# biolab_rev3.net
KiCad netlist of a schematic drawn in Altium Designer
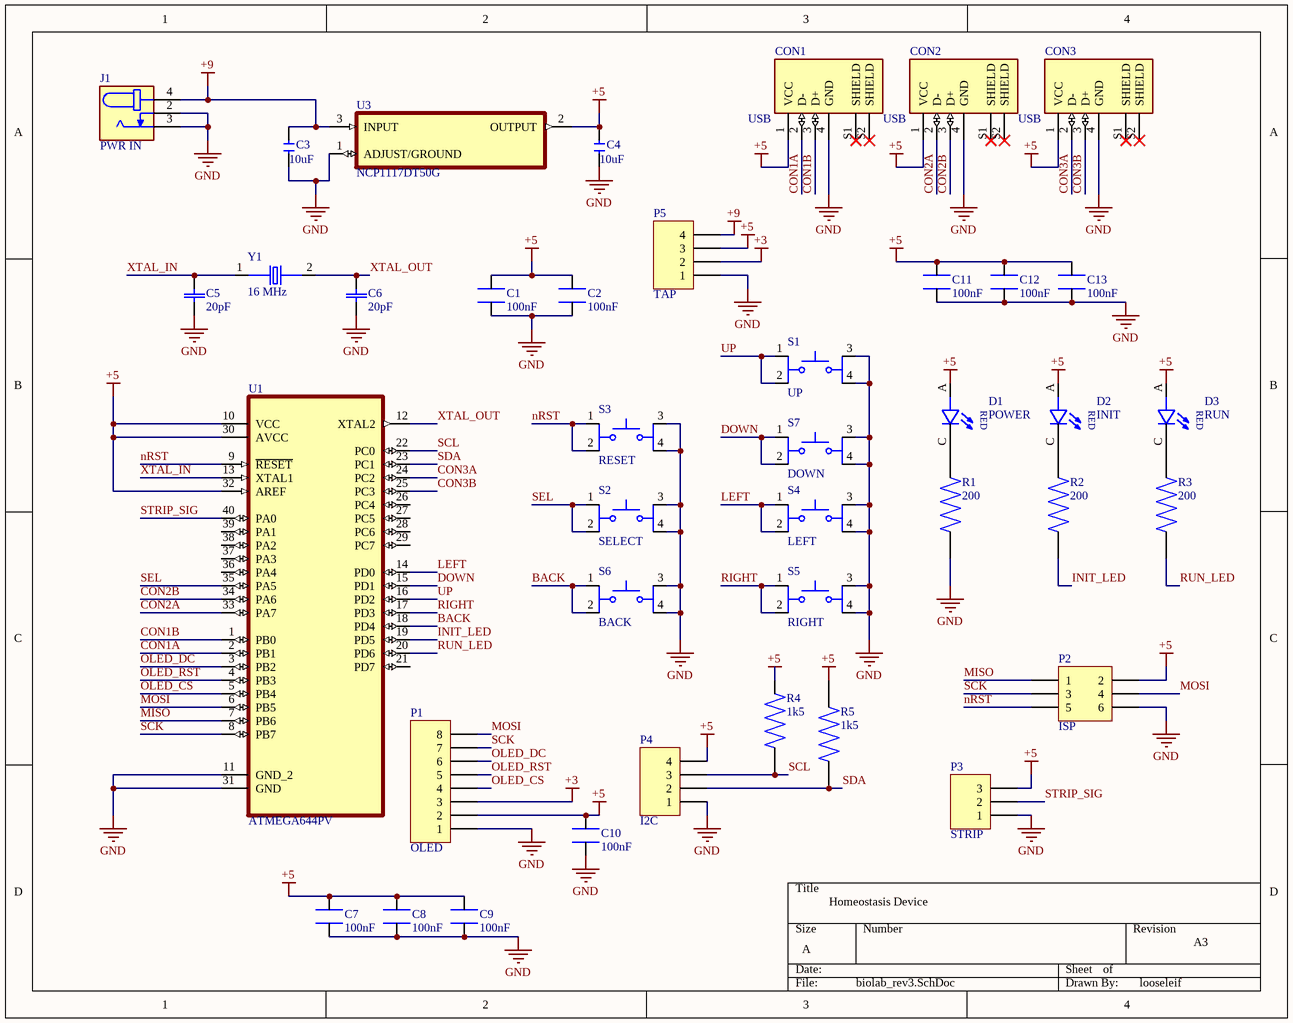
[diagram p0: biolab_rev3.SchDoc]

(export (version "E")
  (design (tool "Eeschema 10.0.6"))
  (components
    (comp (ref "C1")
      (value "100nF")
      (footprint "WCAP-CSST_885382206004")
      (fields
        (field (name "MP") "885382206004")
        (field (name "MF") "{'manufacturer': u'Wurth Electronics Inc'}")
      )
      (libsource (lib "biolab_interface") (part "885382206004"))
    )
    (comp (ref "C2")
      (value "100nF")
      (footprint "WCAP-CSST_885382206004")
      (fields
        (field (name "MP") "885382206004")
        (field (name "MF") "{'manufacturer': u'Wurth Electronics Inc'}")
      )
      (libsource (lib "biolab_interface") (part "885382206004"))
    )
    (comp (ref "C3")
      (value "10uF")
      (footprint "C0603")
      (description "302010103")
      (fields
        (field (name "MP") "CERAMIC-10UF-10V-10%-X5R(0603)")
        (field (name "MF") "{'manufacturer': u'Yageo'}")
      )
      (libsource (lib "SnapEDA_Library") (part "CERAMIC-10UF-10V-10%-X5R(0603)"))
    )
    (comp (ref "C4")
      (value "10uF")
      (footprint "C0603")
      (description "302010103")
      (fields
        (field (name "MP") "CERAMIC-10UF-10V-10%-X5R(0603)")
        (field (name "MF") "{'manufacturer': u'Yageo'}")
      )
      (libsource (lib "SnapEDA_Library") (part "CERAMIC-10UF-10V-10%-X5R(0603)"))
    )
    (comp (ref "C5")
      (value "20pF")
      (footprint "CAPC1608X85N")
      (description "CAPACITOR, 0603")
      (fields (field (name "MP") "C0603C200J5GACTU") (field (name "MF") "{'manufacturer': u'KEMET'}"))
      (libsource (lib "SnapEDA_Library") (part "C0603C200J5GACTU"))
    )
    (comp (ref "C6")
      (value "20pF")
      (footprint "CAPC1608X85N")
      (description "CAPACITOR, 0603")
      (fields (field (name "MP") "C0603C200J5GACTU") (field (name "MF") "{'manufacturer': u'KEMET'}"))
      (libsource (lib "SnapEDA_Library") (part "C0603C200J5GACTU"))
    )
    (comp (ref "C7")
      (value "100nF")
      (footprint "WCAP-CSST_885382206004")
      (fields
        (field (name "MP") "885382206004")
        (field (name "MF") "{'manufacturer': u'Wurth Electronics Inc'}")
      )
      (libsource (lib "biolab_interface") (part "885382206004"))
    )
    (comp (ref "C8")
      (value "100nF")
      (footprint "WCAP-CSST_885382206004")
      (fields
        (field (name "MP") "885382206004")
        (field (name "MF") "{'manufacturer': u'Wurth Electronics Inc'}")
      )
      (libsource (lib "biolab_interface") (part "885382206004"))
    )
    (comp (ref "C9")
      (value "100nF")
      (footprint "WCAP-CSST_885382206004")
      (fields
        (field (name "MP") "885382206004")
        (field (name "MF") "{'manufacturer': u'Wurth Electronics Inc'}")
      )
      (libsource (lib "biolab_interface") (part "885382206004"))
    )
    (comp (ref "C10")
      (value "100nF")
      (footprint "WCAP-CSST_885382206004")
      (fields
        (field (name "MP") "885382206004")
        (field (name "MF") "{'manufacturer': u'Wurth Electronics Inc'}")
      )
      (libsource (lib "biolab_interface") (part "885382206004"))
    )
    (comp (ref "C11")
      (value "100nF")
      (footprint "WCAP-CSST_885382206004")
      (fields
        (field (name "MP") "885382206004")
        (field (name "MF") "{'manufacturer': u'Wurth Electronics Inc'}")
      )
      (libsource (lib "biolab_interface") (part "885382206004"))
    )
    (comp (ref "C12")
      (value "100nF")
      (footprint "WCAP-CSST_885382206004")
      (fields
        (field (name "MP") "885382206004")
        (field (name "MF") "{'manufacturer': u'Wurth Electronics Inc'}")
      )
      (libsource (lib "biolab_interface") (part "885382206004"))
    )
    (comp (ref "C13")
      (value "100nF")
      (footprint "WCAP-CSST_885382206004")
      (fields
        (field (name "MP") "885382206004")
        (field (name "MF") "{'manufacturer': u'Wurth Electronics Inc'}")
      )
      (libsource (lib "biolab_interface") (part "885382206004"))
    )
    (comp (ref "CON1")
      (value "USB")
      (footprint "GCT_USB1130-15-A_REVA")
      (fields
        (field (name "MP") "USB1130-15-A_REVA")
        (field (name "MF") "{'manufacturer': u'Global Connector Technology'}")
      )
      (libsource (lib "SnapEDA_Library") (part "USB1130-15-A_REVA"))
    )
    (comp (ref "CON2")
      (value "USB")
      (footprint "GCT_USB1130-15-A_REVA")
      (fields
        (field (name "MP") "USB1130-15-A_REVA")
        (field (name "MF") "{'manufacturer': u'Global Connector Technology'}")
      )
      (libsource (lib "SnapEDA_Library") (part "USB1130-15-A_REVA"))
    )
    (comp (ref "CON3")
      (value "USB")
      (footprint "GCT_USB1130-15-A_REVA")
      (fields
        (field (name "MP") "USB1130-15-A_REVA")
        (field (name "MF") "{'manufacturer': u'Global Connector Technology'}")
      )
      (libsource (lib "SnapEDA_Library") (part "USB1130-15-A_REVA"))
    )
    (comp (ref "D1")
      (value "POWER")
      (footprint "LED_7012X1")
      (description "Red LED Indication - Discrete 1.7V 0805 (2012 Metric)")
      (fields (field (name "MP") "7012X1") (field (name "MF") "{'manufacturer': u'Visual'}"))
      (libsource (lib "SnapEDA_Library") (part "7012X1"))
    )
    (comp (ref "D2")
      (value "INIT")
      (footprint "LED_7012X1")
      (description "Red LED Indication - Discrete 1.7V 0805 (2012 Metric)")
      (fields (field (name "MP") "7012X1") (field (name "MF") "{'manufacturer': u'Visual'}"))
      (libsource (lib "SnapEDA_Library") (part "7012X1"))
    )
    (comp (ref "D3")
      (value "RUN")
      (footprint "LED_7012X1")
      (description "Red LED Indication - Discrete 1.7V 0805 (2012 Metric)")
      (fields (field (name "MP") "7012X1") (field (name "MF") "{'manufacturer': u'Visual'}"))
      (libsource (lib "SnapEDA_Library") (part "7012X1"))
    )
    (comp (ref "J1")
      (value "PWR IN")
      (footprint "NINIGI_DC-005")
      (description "DC Jack")
      (fields (field (name "MP") "DC-005") (field (name "MF") "{'manufacturer': u'Best Inc.'}"))
      (libsource (lib "SnapEDA_Library") (part "DC-005"))
    )
    (comp (ref "P1")
      (value "OLED")
      (footprint "HDR1X8")
      (description "Header, 8-Pin")
      (fields (field (name "PUBLISHER") "Altium Limited"))
      (libsource (lib "Miscellaneous Connectors") (part "Header 8"))
    )
    (comp (ref "P2")
      (value "ISP")
      (footprint "HDR2X3")
      (description "Header, 3-Pin, Dual row")
      (fields (field (name "PUBLISHER") "Altium Limited"))
      (libsource (lib "Miscellaneous Connectors") (part "Header 3X2"))
    )
    (comp (ref "P3")
      (value "STRIP")
      (footprint "HDR1X3H")
      (description "Header, 3-Pin, Right Angle")
      (fields (field (name "PUBLISHER") "Altium Limited"))
      (libsource (lib "Miscellaneous Connectors") (part "Header 3H"))
    )
    (comp (ref "P4")
      (value "I2C")
      (footprint "HDR1X4H")
      (description "Header, 4-Pin, Right Angle")
      (fields (field (name "PUBLISHER") "Altium Limited"))
      (libsource (lib "Miscellaneous Connectors") (part "Header 4H"))
    )
    (comp (ref "P5")
      (value "TAP")
      (footprint "HDR1X4H")
      (description "Header, 4-Pin, Right Angle")
      (fields (field (name "PUBLISHER") "Altium Limited"))
      (libsource (lib "Miscellaneous Connectors") (part "Header 4H"))
    )
    (comp (ref "R1")
      (value "200")
      (footprint "RESC1608X55N")
      (fields (field (name "MP") "SR0603JR-07200RL") (field (name "MF") "{'manufacturer': u'Yageo'}"))
      (libsource (lib "biolab_interface") (part "SR0603JR-07200RL"))
    )
    (comp (ref "R2")
      (value "200")
      (footprint "RESC1608X55N")
      (fields (field (name "MP") "SR0603JR-07200RL") (field (name "MF") "{'manufacturer': u'Yageo'}"))
      (libsource (lib "biolab_interface") (part "SR0603JR-07200RL"))
    )
    (comp (ref "R3")
      (value "200")
      (footprint "RESC1608X55N")
      (fields (field (name "MP") "SR0603JR-07200RL") (field (name "MF") "{'manufacturer': u'Yageo'}"))
      (libsource (lib "biolab_interface") (part "SR0603JR-07200RL"))
    )
    (comp (ref "R4")
      (value "1k5")
      (footprint "RESC1508X55N")
      (fields (field (name "MP") "TNPW06031K50BXEN") (field (name "MF") "{'manufacturer': u'Vishay'}"))
      (libsource (lib "biolab_interface") (part "TNPW06031K50BXEN"))
    )
    (comp (ref "R5")
      (value "1k5")
      (footprint "RESC1508X55N")
      (fields (field (name "MP") "TNPW06031K50BXEN") (field (name "MF") "{'manufacturer': u'Vishay'}"))
      (libsource (lib "biolab_interface") (part "TNPW06031K50BXEN"))
    )
    (comp (ref "S1")
      (value "UP")
      (footprint "SW_TL3301AF160QG")
      (fields (field (name "MP") "TL3301AF160QG") (field (name "MF") "{'manufacturer': u'E-Switch'}"))
      (libsource (lib "biolab_interface") (part "TL3301AF160QG"))
    )
    (comp (ref "S2")
      (value "SELECT")
      (footprint "SW_TL3301AF160QG")
      (fields (field (name "MP") "TL3301AF160QG") (field (name "MF") "{'manufacturer': u'E-Switch'}"))
      (libsource (lib "biolab_interface") (part "TL3301AF160QG"))
    )
    (comp (ref "S3")
      (value "RESET")
      (footprint "SW_TL3301AF160QG")
      (fields (field (name "MP") "TL3301AF160QG") (field (name "MF") "{'manufacturer': u'E-Switch'}"))
      (libsource (lib "biolab_interface") (part "TL3301AF160QG"))
    )
    (comp (ref "S4")
      (value "LEFT")
      (footprint "SW_TL3301AF160QG")
      (fields (field (name "MP") "TL3301AF160QG") (field (name "MF") "{'manufacturer': u'E-Switch'}"))
      (libsource (lib "biolab_interface") (part "TL3301AF160QG"))
    )
    (comp (ref "S5")
      (value "RIGHT")
      (footprint "SW_TL3301AF160QG")
      (fields (field (name "MP") "TL3301AF160QG") (field (name "MF") "{'manufacturer': u'E-Switch'}"))
      (libsource (lib "biolab_interface") (part "TL3301AF160QG"))
    )
    (comp (ref "S6")
      (value "BACK")
      (footprint "SW_TL3301AF160QG")
      (fields (field (name "MP") "TL3301AF160QG") (field (name "MF") "{'manufacturer': u'E-Switch'}"))
      (libsource (lib "biolab_interface") (part "TL3301AF160QG"))
    )
    (comp (ref "S7")
      (value "DOWN")
      (footprint "SW_TL3301AF160QG")
      (fields (field (name "MP") "TL3301AF160QG") (field (name "MF") "{'manufacturer': u'E-Switch'}"))
      (libsource (lib "biolab_interface") (part "TL3301AF160QG"))
    )
    (comp (ref "U1")
      (value "ATMEGA644PV")
      (footprint "DIP254P1524X483-40")
      (description "8-bit Microcontroller with In-System Programmable  Flash")
      (fields
        (field (name "MP") "ATMEGA644PV-10PU")
        (field (name "MF") "{'manufacturer': u'Microchip Technology'}")
      )
      (libsource (lib "SnapEDA_Library") (part "ATMEGA644PV-10PU"))
    )
    (comp (ref "U3")
      (value "NCP1117DT50G")
      (footprint "DPAK229P990X238-4N")
      (fields (field (name "MF") "{'manufacturer': u'ON Semiconductor'}"))
      (libsource (lib "SnapEDA_Library") (part "NCP1117DT50G"))
    )
    (comp (ref "Y1")
      (value "16 MHz")
      (footprint "XTAL_FOXSDLF/160-20")
      (description "Crystal 16MHz 20pF 2-Pin HC-49/SD")
      (fields (field (name "MP") "FOXSDLF/160-20") (field (name "MF") "{'manufacturer': u'Fox Electronics'}"))
      (libsource (lib "SnapEDA_Library") (part "FOXSDLF/160-20"))
    )
  )
  (nets
    (net (code "1") (name "+3") (class "Default")
      (node (ref "P1") (pin "3") (pinfunction "3_3") (pintype "passive"))
      (node (ref "P5") (pin "2") (pinfunction "2_2") (pintype "passive"))
    )
    (net (code "2") (name "+5") (class "Default")
      (node (ref "C1") (pin "2") (pinfunction "2_2") (pintype "passive"))
      (node (ref "C10") (pin "2") (pinfunction "2_2") (pintype "passive"))
      (node (ref "C11") (pin "2") (pinfunction "2_2") (pintype "passive"))
      (node (ref "C12") (pin "2") (pinfunction "2_2") (pintype "passive"))
      (node (ref "C13") (pin "2") (pinfunction "2_2") (pintype "passive"))
      (node (ref "C2") (pin "2") (pinfunction "2_2") (pintype "passive"))
      (node (ref "C4") (pin "2") (pinfunction "2_2") (pintype "passive"))
      (node (ref "C7") (pin "2") (pinfunction "2_2") (pintype "passive"))
      (node (ref "C8") (pin "2") (pinfunction "2_2") (pintype "passive"))
      (node (ref "C9") (pin "2") (pinfunction "2_2") (pintype "passive"))
      (node (ref "CON1") (pin "1") (pinfunction "VCC_1") (pintype "power_in"))
      (node (ref "CON2") (pin "1") (pinfunction "VCC_1") (pintype "power_in"))
      (node (ref "CON3") (pin "1") (pinfunction "VCC_1") (pintype "power_in"))
      (node (ref "D1") (pin "A") (pinfunction "A_A") (pintype "passive"))
      (node (ref "D2") (pin "A") (pinfunction "A_A") (pintype "passive"))
      (node (ref "D3") (pin "A") (pinfunction "A_A") (pintype "passive"))
      (node (ref "P1") (pin "2") (pinfunction "2_2") (pintype "passive"))
      (node (ref "P2") (pin "2") (pinfunction "2_2") (pintype "passive"))
      (node (ref "P3") (pin "3") (pinfunction "3_3") (pintype "passive"))
      (node (ref "P4") (pin "4") (pinfunction "4_4") (pintype "passive"))
      (node (ref "P5") (pin "3") (pinfunction "3_3") (pintype "passive"))
      (node (ref "R4") (pin "2") (pinfunction "2_2") (pintype "passive"))
      (node (ref "R5") (pin "2") (pinfunction "2_2") (pintype "passive"))
      (node (ref "U1") (pin "10") (pinfunction "VCC_10") (pintype "power_in"))
      (node (ref "U1") (pin "30") (pinfunction "AVCC_30") (pintype "power_in"))
      (node (ref "U1") (pin "32") (pinfunction "AREF_32") (pintype "input"))
      (node (ref "U3") (pin "2") (pinfunction "OUTPUT_2") (pintype "output"))
    )
    (net (code "3") (name "+9") (class "Default")
      (node (ref "C3") (pin "2") (pinfunction "2_2") (pintype "passive"))
      (node (ref "J1") (pin "4") (pinfunction "2_4") (pintype "passive"))
      (node (ref "P5") (pin "4") (pinfunction "4_4") (pintype "passive"))
      (node (ref "U3") (pin "3") (pinfunction "INPUT_3") (pintype "input"))
    )
    (net (code "4") (name "/BACK") (class "Default")
      (node (ref "S6") (pin "1") (pinfunction "1_1") (pintype "passive"))
      (node (ref "S6") (pin "2") (pinfunction "2_2") (pintype "passive"))
      (node (ref "U1") (pin "18") (pinfunction "PD4_18") (pintype "bidirectional"))
    )
    (net (code "5") (name "/CON1A") (class "Default")
      (node (ref "CON1") (pin "2") (pinfunction "D-_2") (pintype "bidirectional"))
      (node (ref "U1") (pin "2") (pinfunction "PB1_2") (pintype "bidirectional"))
    )
    (net (code "6") (name "/CON1B") (class "Default")
      (node (ref "CON1") (pin "3") (pinfunction "D+_3") (pintype "bidirectional"))
      (node (ref "U1") (pin "1") (pinfunction "PB0_1") (pintype "bidirectional"))
    )
    (net (code "7") (name "/CON2A") (class "Default")
      (node (ref "CON2") (pin "2") (pinfunction "D-_2") (pintype "bidirectional"))
      (node (ref "U1") (pin "33") (pinfunction "PA7_33") (pintype "bidirectional"))
    )
    (net (code "8") (name "/CON2B") (class "Default")
      (node (ref "CON2") (pin "3") (pinfunction "D+_3") (pintype "bidirectional"))
      (node (ref "U1") (pin "34") (pinfunction "PA6_34") (pintype "bidirectional"))
    )
    (net (code "9") (name "/CON3A") (class "Default")
      (node (ref "CON3") (pin "2") (pinfunction "D-_2") (pintype "bidirectional"))
      (node (ref "U1") (pin "24") (pinfunction "PC2_24") (pintype "bidirectional"))
    )
    (net (code "10") (name "/CON3B") (class "Default")
      (node (ref "CON3") (pin "3") (pinfunction "D+_3") (pintype "bidirectional"))
      (node (ref "U1") (pin "25") (pinfunction "PC3_25") (pintype "bidirectional"))
    )
    (net (code "11") (name "/DOWN") (class "Default")
      (node (ref "S7") (pin "1") (pinfunction "1_1") (pintype "passive"))
      (node (ref "S7") (pin "2") (pinfunction "2_2") (pintype "passive"))
      (node (ref "U1") (pin "15") (pinfunction "PD1_15") (pintype "bidirectional"))
    )
    (net (code "12") (name "/INIT_LED") (class "Default")
      (node (ref "R2") (pin "1") (pinfunction "1_1") (pintype "passive"))
      (node (ref "U1") (pin "19") (pinfunction "PD5_19") (pintype "bidirectional"))
    )
    (net (code "13") (name "/LEFT") (class "Default")
      (node (ref "S4") (pin "1") (pinfunction "1_1") (pintype "passive"))
      (node (ref "S4") (pin "2") (pinfunction "2_2") (pintype "passive"))
      (node (ref "U1") (pin "14") (pinfunction "PD0_14") (pintype "bidirectional"))
    )
    (net (code "14") (name "/MISO") (class "Default")
      (node (ref "P2") (pin "1") (pinfunction "1_1") (pintype "passive"))
      (node (ref "U1") (pin "7") (pinfunction "PB6_7") (pintype "bidirectional"))
    )
    (net (code "15") (name "/MOSI") (class "Default")
      (node (ref "P1") (pin "8") (pinfunction "8_8") (pintype "passive"))
      (node (ref "P2") (pin "4") (pinfunction "4_4") (pintype "passive"))
      (node (ref "U1") (pin "6") (pinfunction "PB5_6") (pintype "bidirectional"))
    )
    (net (code "16") (name "/OLED_CS") (class "Default")
      (node (ref "P1") (pin "4") (pinfunction "4_4") (pintype "passive"))
      (node (ref "U1") (pin "5") (pinfunction "PB4_5") (pintype "bidirectional"))
    )
    (net (code "17") (name "/OLED_DC") (class "Default")
      (node (ref "P1") (pin "6") (pinfunction "6_6") (pintype "passive"))
      (node (ref "U1") (pin "3") (pinfunction "PB2_3") (pintype "bidirectional"))
    )
    (net (code "18") (name "/OLED_RST") (class "Default")
      (node (ref "P1") (pin "5") (pinfunction "5_5") (pintype "passive"))
      (node (ref "U1") (pin "4") (pinfunction "PB3_4") (pintype "bidirectional"))
    )
    (net (code "19") (name "/RIGHT") (class "Default")
      (node (ref "S5") (pin "1") (pinfunction "1_1") (pintype "passive"))
      (node (ref "S5") (pin "2") (pinfunction "2_2") (pintype "passive"))
      (node (ref "U1") (pin "17") (pinfunction "PD3_17") (pintype "bidirectional"))
    )
    (net (code "20") (name "/RUN_LED") (class "Default")
      (node (ref "R3") (pin "1") (pinfunction "1_1") (pintype "passive"))
      (node (ref "U1") (pin "20") (pinfunction "PD6_20") (pintype "bidirectional"))
    )
    (net (code "21") (name "/SCK") (class "Default")
      (node (ref "P1") (pin "7") (pinfunction "7_7") (pintype "passive"))
      (node (ref "P2") (pin "3") (pinfunction "3_3") (pintype "passive"))
      (node (ref "U1") (pin "8") (pinfunction "PB7_8") (pintype "bidirectional"))
    )
    (net (code "22") (name "/SCL") (class "Default")
      (node (ref "P4") (pin "3") (pinfunction "3_3") (pintype "passive"))
      (node (ref "R4") (pin "1") (pinfunction "1_1") (pintype "passive"))
      (node (ref "U1") (pin "22") (pinfunction "PC0_22") (pintype "bidirectional"))
    )
    (net (code "23") (name "/SDA") (class "Default")
      (node (ref "P4") (pin "2") (pinfunction "2_2") (pintype "passive"))
      (node (ref "R5") (pin "1") (pinfunction "1_1") (pintype "passive"))
      (node (ref "U1") (pin "23") (pinfunction "PC1_23") (pintype "bidirectional"))
    )
    (net (code "24") (name "/SEL") (class "Default")
      (node (ref "S2") (pin "1") (pinfunction "1_1") (pintype "passive"))
      (node (ref "S2") (pin "2") (pinfunction "2_2") (pintype "passive"))
      (node (ref "U1") (pin "35") (pinfunction "PA5_35") (pintype "bidirectional"))
    )
    (net (code "25") (name "/STRIP_SIG") (class "Default")
      (node (ref "P3") (pin "2") (pinfunction "2_2") (pintype "passive"))
      (node (ref "U1") (pin "40") (pinfunction "PA0_40") (pintype "bidirectional"))
    )
    (net (code "26") (name "/UP") (class "Default")
      (node (ref "S1") (pin "1") (pinfunction "1_1") (pintype "passive"))
      (node (ref "S1") (pin "2") (pinfunction "2_2") (pintype "passive"))
      (node (ref "U1") (pin "16") (pinfunction "PD2_16") (pintype "bidirectional"))
    )
    (net (code "27") (name "/XTAL_IN") (class "Default")
      (node (ref "C5") (pin "2") (pinfunction "C2_2") (pintype "passive"))
      (node (ref "U1") (pin "13") (pinfunction "XTAL1_13") (pintype "input"))
      (node (ref "Y1") (pin "1") (pinfunction "1_1") (pintype "passive"))
    )
    (net (code "28") (name "/XTAL_OUT") (class "Default")
      (node (ref "C6") (pin "2") (pinfunction "C2_2") (pintype "passive"))
      (node (ref "U1") (pin "12") (pinfunction "XTAL2_12") (pintype "output"))
      (node (ref "Y1") (pin "2") (pinfunction "2_2") (pintype "passive"))
    )
    (net (code "29") (name "/nRST") (class "Default")
      (node (ref "P2") (pin "5") (pinfunction "5_5") (pintype "passive"))
      (node (ref "S3") (pin "1") (pinfunction "1_1") (pintype "passive"))
      (node (ref "S3") (pin "2") (pinfunction "2_2") (pintype "passive"))
      (node (ref "U1") (pin "9") (pinfunction "~{RESET}_9") (pintype "input"))
    )
    (net (code "30") (name "GND") (class "Default")
      (node (ref "C1") (pin "1") (pinfunction "1_1") (pintype "passive"))
      (node (ref "C10") (pin "1") (pinfunction "1_1") (pintype "passive"))
      (node (ref "C11") (pin "1") (pinfunction "1_1") (pintype "passive"))
      (node (ref "C12") (pin "1") (pinfunction "1_1") (pintype "passive"))
      (node (ref "C13") (pin "1") (pinfunction "1_1") (pintype "passive"))
      (node (ref "C2") (pin "1") (pinfunction "1_1") (pintype "passive"))
      (node (ref "C3") (pin "1") (pinfunction "1_1") (pintype "passive"))
      (node (ref "C4") (pin "1") (pinfunction "1_1") (pintype "passive"))
      (node (ref "C5") (pin "1") (pinfunction "C1_1") (pintype "passive"))
      (node (ref "C6") (pin "1") (pinfunction "C1_1") (pintype "passive"))
      (node (ref "C7") (pin "1") (pinfunction "1_1") (pintype "passive"))
      (node (ref "C8") (pin "1") (pinfunction "1_1") (pintype "passive"))
      (node (ref "C9") (pin "1") (pinfunction "1_1") (pintype "passive"))
      (node (ref "CON1") (pin "4") (pinfunction "GND_4") (pintype "power_in"))
      (node (ref "CON2") (pin "4") (pinfunction "GND_4") (pintype "power_in"))
      (node (ref "CON3") (pin "4") (pinfunction "GND_4") (pintype "power_in"))
      (node (ref "J1") (pin "2") (pinfunction "4_2") (pintype "passive"))
      (node (ref "J1") (pin "3") (pinfunction "5_3") (pintype "passive"))
      (node (ref "P1") (pin "1") (pinfunction "1_1") (pintype "passive"))
      (node (ref "P2") (pin "6") (pinfunction "6_6") (pintype "passive"))
      (node (ref "P3") (pin "1") (pinfunction "1_1") (pintype "passive"))
      (node (ref "P4") (pin "1") (pinfunction "1_1") (pintype "passive"))
      (node (ref "P5") (pin "1") (pinfunction "1_1") (pintype "passive"))
      (node (ref "R1") (pin "1") (pinfunction "1_1") (pintype "passive"))
      (node (ref "S1") (pin "3") (pinfunction "3_3") (pintype "passive"))
      (node (ref "S1") (pin "4") (pinfunction "4_4") (pintype "passive"))
      (node (ref "S2") (pin "3") (pinfunction "3_3") (pintype "passive"))
      (node (ref "S2") (pin "4") (pinfunction "4_4") (pintype "passive"))
      (node (ref "S3") (pin "3") (pinfunction "3_3") (pintype "passive"))
      (node (ref "S3") (pin "4") (pinfunction "4_4") (pintype "passive"))
      (node (ref "S4") (pin "3") (pinfunction "3_3") (pintype "passive"))
      (node (ref "S4") (pin "4") (pinfunction "4_4") (pintype "passive"))
      (node (ref "S5") (pin "3") (pinfunction "3_3") (pintype "passive"))
      (node (ref "S5") (pin "4") (pinfunction "4_4") (pintype "passive"))
      (node (ref "S6") (pin "3") (pinfunction "3_3") (pintype "passive"))
      (node (ref "S6") (pin "4") (pinfunction "4_4") (pintype "passive"))
      (node (ref "S7") (pin "3") (pinfunction "3_3") (pintype "passive"))
      (node (ref "S7") (pin "4") (pinfunction "4_4") (pintype "passive"))
      (node (ref "U1") (pin "11") (pinfunction "GND_2_11") (pintype "passive"))
      (node (ref "U1") (pin "31") (pinfunction "GND_31") (pintype "passive"))
      (node (ref "U3") (pin "1") (pinfunction "ADJUST/GROUND_1") (pintype "bidirectional"))
    )
    (net (code "31") (name "Net-(D1-PadC)") (class "Default")
      (node (ref "D1") (pin "C") (pinfunction "C_C") (pintype "passive"))
      (node (ref "R1") (pin "2") (pinfunction "2_2") (pintype "passive"))
    )
    (net (code "32") (name "Net-(D2-PadC)") (class "Default")
      (node (ref "D2") (pin "C") (pinfunction "C_C") (pintype "passive"))
      (node (ref "R2") (pin "2") (pinfunction "2_2") (pintype "passive"))
    )
    (net (code "33") (name "Net-(D3-PadC)") (class "Default")
      (node (ref "D3") (pin "C") (pinfunction "C_C") (pintype "passive"))
      (node (ref "R3") (pin "2") (pinfunction "2_2") (pintype "passive"))
    )
    (net (code "34") (name "unconnected-(CON1-SHIELD-PadS1)") (class "Default")
      (node (ref "CON1") (pin "S1") (pinfunction "SHIELD_S1") (pintype "passive+no_connect"))
    )
    (net (code "35") (name "unconnected-(CON1-SHIELD-PadS2)") (class "Default")
      (node (ref "CON1") (pin "S2") (pinfunction "SHIELD_S2") (pintype "passive+no_connect"))
    )
    (net (code "36") (name "unconnected-(CON2-SHIELD-PadS1)") (class "Default")
      (node (ref "CON2") (pin "S1") (pinfunction "SHIELD_S1") (pintype "passive+no_connect"))
    )
    (net (code "37") (name "unconnected-(CON2-SHIELD-PadS2)") (class "Default")
      (node (ref "CON2") (pin "S2") (pinfunction "SHIELD_S2") (pintype "passive+no_connect"))
    )
    (net (code "38") (name "unconnected-(CON3-SHIELD-PadS1)") (class "Default")
      (node (ref "CON3") (pin "S1") (pinfunction "SHIELD_S1") (pintype "passive+no_connect"))
    )
    (net (code "39") (name "unconnected-(CON3-SHIELD-PadS2)") (class "Default")
      (node (ref "CON3") (pin "S2") (pinfunction "SHIELD_S2") (pintype "passive+no_connect"))
    )
    (net (code "40") (name "unconnected-(U1-PA1-Pad39)") (class "Default")
      (node (ref "U1") (pin "39") (pinfunction "PA1_39") (pintype "bidirectional"))
    )
    (net (code "41") (name "unconnected-(U1-PA2-Pad38)") (class "Default")
      (node (ref "U1") (pin "38") (pinfunction "PA2_38") (pintype "bidirectional"))
    )
    (net (code "42") (name "unconnected-(U1-PA3-Pad37)") (class "Default")
      (node (ref "U1") (pin "37") (pinfunction "PA3_37") (pintype "bidirectional"))
    )
    (net (code "43") (name "unconnected-(U1-PA4-Pad36)") (class "Default")
      (node (ref "U1") (pin "36") (pinfunction "PA4_36") (pintype "bidirectional"))
    )
    (net (code "44") (name "unconnected-(U1-PC4-Pad26)") (class "Default")
      (node (ref "U1") (pin "26") (pinfunction "PC4_26") (pintype "bidirectional"))
    )
    (net (code "45") (name "unconnected-(U1-PC5-Pad27)") (class "Default")
      (node (ref "U1") (pin "27") (pinfunction "PC5_27") (pintype "bidirectional"))
    )
    (net (code "46") (name "unconnected-(U1-PC6-Pad28)") (class "Default")
      (node (ref "U1") (pin "28") (pinfunction "PC6_28") (pintype "bidirectional"))
    )
    (net (code "47") (name "unconnected-(U1-PC7-Pad29)") (class "Default")
      (node (ref "U1") (pin "29") (pinfunction "PC7_29") (pintype "bidirectional"))
    )
    (net (code "48") (name "unconnected-(U1-PD7-Pad21)") (class "Default")
      (node (ref "U1") (pin "21") (pinfunction "PD7_21") (pintype "bidirectional"))
    )
  )
)
